# mix_rxd.net
KiCad netlist of a schematic drawn in Altium Designer
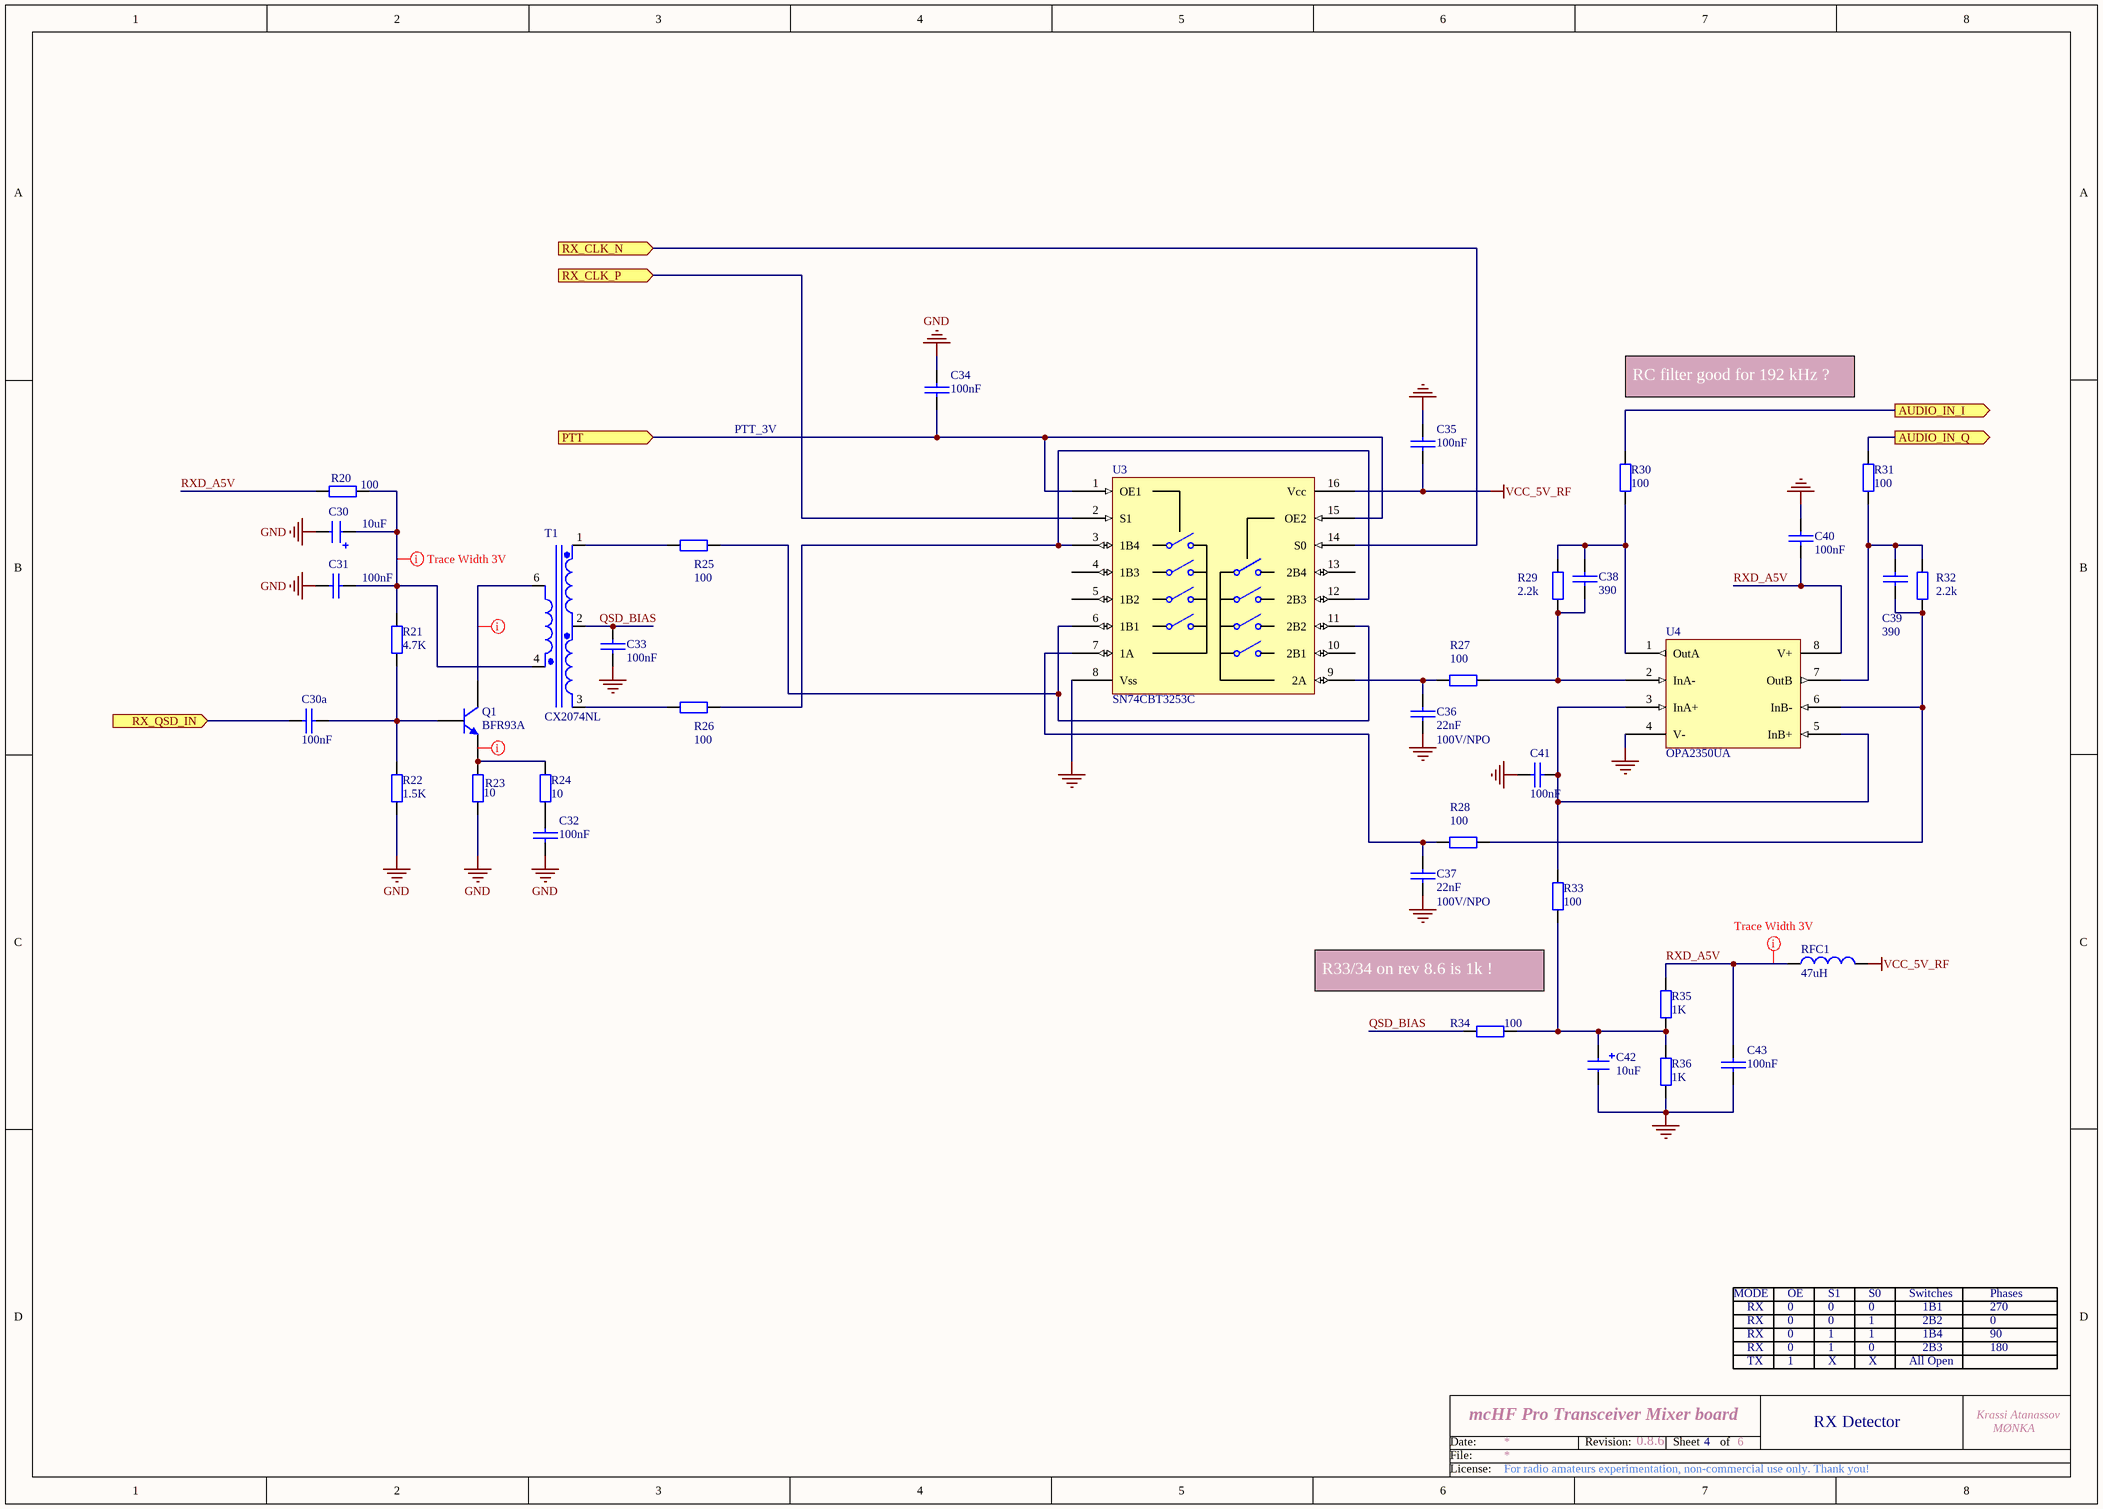
[diagram p0: mix_rxd.SchDoc]

(export (version "E")
  (design (tool "Eeschema 10.0.6"))
  (components
    (comp (ref "C30")
      (value "10uF")
      (footprint "1206_Elec_Cap")
      (description "Electrolitic capacitor")
      (libsource (lib "mcHF_rf") (part "CAP-POL"))
    )
    (comp (ref "C30a")
      (value "100nF")
      (footprint "0805")
      (description "Capacitor")
      (libsource (lib "mcHF_rf") (part "CAP"))
    )
    (comp (ref "C31")
      (value "100nF")
      (footprint "0805")
      (description "Capacitor")
      (libsource (lib "mcHF_rf") (part "CAP"))
    )
    (comp (ref "C32")
      (value "100nF")
      (footprint "0805")
      (description "Capacitor")
      (libsource (lib "mcHF_rf") (part "CAP"))
    )
    (comp (ref "C33")
      (value "100nF")
      (footprint "0805")
      (description "Capacitor")
      (libsource (lib "mcHF_rf") (part "CAP"))
    )
    (comp (ref "C34")
      (value "100nF")
      (footprint "0805")
      (description "Capacitor")
      (libsource (lib "mcHF_rf") (part "CAP"))
    )
    (comp (ref "C35")
      (value "100nF")
      (footprint "0805")
      (description "Capacitor")
      (libsource (lib "mcHF_rf") (part "CAP"))
    )
    (comp (ref "C36")
      (value "22nF")
      (footprint "CAP_B")
      (description "Capacitor")
      (fields (field (name "VOLTAGE") "100V/NPO"))
      (libsource (lib "mcHF_rf") (part "CAP"))
    )
    (comp (ref "C37")
      (value "22nF")
      (footprint "CAP_B")
      (description "Capacitor")
      (fields (field (name "VOLTAGE") "100V/NPO"))
      (libsource (lib "mcHF_rf") (part "CAP"))
    )
    (comp (ref "C38")
      (value "390")
      (footprint "0805")
      (description "Capacitor")
      (libsource (lib "mcHF_rf") (part "CAP"))
    )
    (comp (ref "C39")
      (value "390")
      (footprint "0805")
      (description "Capacitor")
      (libsource (lib "mcHF_rf") (part "CAP"))
    )
    (comp (ref "C40")
      (value "100nF")
      (footprint "0805")
      (description "Capacitor")
      (libsource (lib "mcHF_rf") (part "CAP"))
    )
    (comp (ref "C41")
      (value "100nF")
      (footprint "0805")
      (description "Capacitor")
      (libsource (lib "mcHF_rf") (part "CAP"))
    )
    (comp (ref "C42")
      (value "10uF")
      (footprint "1206_Elec_Cap")
      (description "Electrolitic capacitor")
      (libsource (lib "mcHF_rf") (part "CAP-POL"))
    )
    (comp (ref "C43")
      (value "100nF")
      (footprint "0805")
      (description "Capacitor")
      (libsource (lib "mcHF_rf") (part "CAP"))
    )
    (comp (ref "Q1")
      (value "BFR93A")
      (footprint "SOT-23")
      (description "TRANSISTOR, RF, NPN, 12V, 0.035MA,SOT-23")
      (libsource (lib "mcHF_rf") (part "BFR93A"))
    )
    (comp (ref "R20")
      (value "100")
      (footprint "0805")
      (description "Resistor")
      (libsource (lib "") (part "RES_3"))
    )
    (comp (ref "R21")
      (value "4.7K")
      (footprint "0805")
      (description "Resistor")
      (libsource (lib "") (part "RES_2"))
    )
    (comp (ref "R22")
      (value "1.5K")
      (footprint "0805")
      (description "Resistor")
      (libsource (lib "") (part "RES_2"))
    )
    (comp (ref "R23")
      (value "10")
      (footprint "0805")
      (description "Resistor")
      (libsource (lib "mcHF_rf") (part "RES"))
    )
    (comp (ref "R24")
      (value "10")
      (footprint "0805")
      (description "Resistor")
      (libsource (lib "mcHF_rf") (part "RES"))
    )
    (comp (ref "R25")
      (value "100")
      (footprint "0805")
      (description "Resistor")
      (libsource (lib "") (part "RES_3"))
    )
    (comp (ref "R26")
      (value "100")
      (footprint "0805")
      (description "Resistor")
      (libsource (lib "") (part "RES_3"))
    )
    (comp (ref "R27")
      (value "100")
      (footprint "0805")
      (description "Resistor")
      (libsource (lib "") (part "RES_3"))
    )
    (comp (ref "R28")
      (value "100")
      (footprint "0805")
      (description "Resistor")
      (libsource (lib "") (part "RES_3"))
    )
    (comp (ref "R29")
      (value "2.2k")
      (footprint "0805")
      (description "Resistor")
      (libsource (lib "mcHF_rf") (part "RES"))
    )
    (comp (ref "R30")
      (value "100")
      (footprint "0805")
      (description "Resistor")
      (libsource (lib "mcHF_rf") (part "RES"))
    )
    (comp (ref "R31")
      (value "100")
      (footprint "0805")
      (description "Resistor")
      (libsource (lib "mcHF_rf") (part "RES"))
    )
    (comp (ref "R32")
      (value "2.2k")
      (footprint "0805")
      (description "Resistor")
      (libsource (lib "mcHF_rf") (part "RES"))
    )
    (comp (ref "R33")
      (value "100")
      (footprint "0805")
      (description "Resistor")
      (libsource (lib "mcHF_rf") (part "RES"))
    )
    (comp (ref "R34")
      (value "100")
      (footprint "0805")
      (description "Resistor")
      (libsource (lib "") (part "RES_1"))
    )
    (comp (ref "R35")
      (value "1K")
      (footprint "0805")
      (description "Resistor")
      (libsource (lib "mcHF_rf") (part "RES"))
    )
    (comp (ref "R36")
      (value "1K")
      (footprint "0805")
      (description "Resistor")
      (libsource (lib "mcHF_rf") (part "RES"))
    )
    (comp (ref "RFC1")
      (value "47uH")
      (footprint "0805")
      (description "INDUCTOR, SIGNAL LINE, 4.7UH, 1005")
      (libsource (lib "mcHF_rf") (part "TDK-NLV25T"))
    )
    (comp (ref "T1")
      (value "CX2074NL")
      (footprint "SOP5_NEW1")
      (description "Wideband RF Transformer 1:4")
      (libsource (lib "mcHF_rf") (part "CX2074NL"))
    )
    (comp (ref "U3")
      (value "SN74CBT3253C")
      (footprint "SO-16-Pro")
      (description "Dual 4:1 Demux/Analog Switch")
      (libsource (lib "mcHF_rf") (part "SN74CBT3253C"))
    )
    (comp (ref "U4")
      (value "OPA2350UA")
      (footprint "SO-8")
      (description "High Speed, Single Supply OpAmp")
      (libsource (lib "mcHF_rf") (part "OPA2350UA"))
    )
  )
  (nets
    (net (code "1") (name "/AUDIO_IN_I") (class "Default")
      (node (ref "R30") (pin "2") (pinfunction "2_2") (pintype "passive"))
    )
    (net (code "2") (name "/AUDIO_IN_Q") (class "Default")
      (node (ref "R31") (pin "2") (pinfunction "2_2") (pintype "passive"))
    )
    (net (code "3") (name "/PTT") (class "Default")
      (node (ref "C34") (pin "1") (pinfunction "1_1") (pintype "passive"))
      (node (ref "U3") (pin "1") (pinfunction "OE1_1") (pintype "input"))
      (node (ref "U3") (pin "15") (pinfunction "OE2_15") (pintype "input"))
    )
    (net (code "4") (name "/QSD_BIAS") (class "Default")
      (node (ref "C33") (pin "1") (pinfunction "1_1") (pintype "passive"))
      (node (ref "R34") (pin "2") (pinfunction "2_2") (pintype "passive"))
      (node (ref "T1") (pin "2") (pinfunction "SecCmn_2") (pintype "passive"))
    )
    (net (code "5") (name "/RXD_A5V") (class "Default")
      (node (ref "C40") (pin "2") (pinfunction "2_2") (pintype "passive"))
      (node (ref "C43") (pin "2") (pinfunction "2_2") (pintype "passive"))
      (node (ref "R20") (pin "1") (pinfunction "1_1") (pintype "passive"))
      (node (ref "R35") (pin "2") (pinfunction "2_2") (pintype "passive"))
      (node (ref "RFC1") (pin "1") (pinfunction "1_1") (pintype "passive"))
      (node (ref "U4") (pin "8") (pinfunction "V+_8") (pintype "power_in"))
    )
    (net (code "6") (name "/RX_CLK_N") (class "Default")
      (node (ref "U3") (pin "14") (pinfunction "S0_14") (pintype "input"))
    )
    (net (code "7") (name "/RX_CLK_P") (class "Default")
      (node (ref "U3") (pin "2") (pinfunction "S1_2") (pintype "input"))
    )
    (net (code "8") (name "/RX_QSD_IN") (class "Default")
      (node (ref "C30a") (pin "1") (pinfunction "1_1") (pintype "passive"))
    )
    (net (code "9") (name "GND") (class "Default")
      (node (ref "C30") (pin "2") (pinfunction "2_2") (pintype "passive"))
      (node (ref "C31") (pin "2") (pinfunction "2_2") (pintype "passive"))
      (node (ref "C32") (pin "1") (pinfunction "1_1") (pintype "passive"))
      (node (ref "C33") (pin "2") (pinfunction "2_2") (pintype "passive"))
      (node (ref "C34") (pin "2") (pinfunction "2_2") (pintype "passive"))
      (node (ref "C35") (pin "2") (pinfunction "2_2") (pintype "passive"))
      (node (ref "C36") (pin "2") (pinfunction "2_2") (pintype "passive"))
      (node (ref "C37") (pin "2") (pinfunction "2_2") (pintype "passive"))
      (node (ref "C40") (pin "1") (pinfunction "1_1") (pintype "passive"))
      (node (ref "C41") (pin "2") (pinfunction "2_2") (pintype "passive"))
      (node (ref "C42") (pin "2") (pinfunction "2_2") (pintype "passive"))
      (node (ref "C43") (pin "1") (pinfunction "1_1") (pintype "passive"))
      (node (ref "R22") (pin "2") (pinfunction "2_2") (pintype "passive"))
      (node (ref "R23") (pin "1") (pinfunction "1_1") (pintype "passive"))
      (node (ref "R36") (pin "1") (pinfunction "1_1") (pintype "passive"))
      (node (ref "U3") (pin "8") (pinfunction "Vss_8") (pintype "power_in"))
      (node (ref "U4") (pin "4") (pinfunction "V-_4") (pintype "power_in"))
    )
    (net (code "10") (name "Net-(C32-Pad2)") (class "Default")
      (node (ref "C32") (pin "2") (pinfunction "2_2") (pintype "passive"))
      (node (ref "R24") (pin "1") (pinfunction "1_1") (pintype "passive"))
    )
    (net (code "11") (name "Net-(C42-Pad1)") (class "Default")
      (node (ref "C42") (pin "1") (pinfunction "1_1") (pintype "passive"))
      (node (ref "R33") (pin "1") (pinfunction "1_1") (pintype "passive"))
      (node (ref "R34") (pin "1") (pinfunction "1_1") (pintype "passive"))
      (node (ref "R35") (pin "1") (pinfunction "1_1") (pintype "passive"))
      (node (ref "R36") (pin "2") (pinfunction "2_2") (pintype "passive"))
    )
    (net (code "12") (name "Net-(Q1-B)") (class "Default")
      (node (ref "C30a") (pin "2") (pinfunction "2_2") (pintype "passive"))
      (node (ref "Q1") (pin "1") (pinfunction "B_1") (pintype "passive"))
      (node (ref "R21") (pin "2") (pinfunction "2_2") (pintype "passive"))
      (node (ref "R22") (pin "1") (pinfunction "1_1") (pintype "passive"))
    )
    (net (code "13") (name "Net-(Q1-C)") (class "Default")
      (node (ref "Q1") (pin "3") (pinfunction "C_3") (pintype "passive"))
      (node (ref "T1") (pin "6") (pinfunction "Pri+_6") (pintype "passive"))
    )
    (net (code "14") (name "Net-(Q1-E)") (class "Default")
      (node (ref "Q1") (pin "2") (pinfunction "E_2") (pintype "passive"))
      (node (ref "R23") (pin "2") (pinfunction "2_2") (pintype "passive"))
      (node (ref "R24") (pin "2") (pinfunction "2_2") (pintype "passive"))
    )
    (net (code "15") (name "Net-(T1-Pri-)") (class "Default")
      (node (ref "C30") (pin "1") (pinfunction "1_1") (pintype "passive"))
      (node (ref "C31") (pin "1") (pinfunction "1_1") (pintype "passive"))
      (node (ref "R20") (pin "2") (pinfunction "2_2") (pintype "passive"))
      (node (ref "R21") (pin "1") (pinfunction "1_1") (pintype "passive"))
      (node (ref "T1") (pin "4") (pinfunction "Pri-_4") (pintype "passive"))
    )
    (net (code "16") (name "Net-(T1-Sec0)") (class "Default")
      (node (ref "R25") (pin "1") (pinfunction "1_1") (pintype "passive"))
      (node (ref "T1") (pin "1") (pinfunction "Sec0_1") (pintype "passive"))
    )
    (net (code "17") (name "Net-(T1-Sec180)") (class "Default")
      (node (ref "R26") (pin "1") (pinfunction "1_1") (pintype "passive"))
      (node (ref "T1") (pin "3") (pinfunction "Sec180_3") (pintype "passive"))
    )
    (net (code "18") (name "Net-(U3-1A)") (class "Default")
      (node (ref "C37") (pin "1") (pinfunction "1_1") (pintype "passive"))
      (node (ref "R28") (pin "1") (pinfunction "1_1") (pintype "passive"))
      (node (ref "U3") (pin "7") (pinfunction "1A_7") (pintype "bidirectional"))
    )
    (net (code "19") (name "Net-(U3-1B1)") (class "Default")
      (node (ref "R25") (pin "2") (pinfunction "2_2") (pintype "passive"))
      (node (ref "U3") (pin "11") (pinfunction "2B2_11") (pintype "bidirectional"))
      (node (ref "U3") (pin "6") (pinfunction "1B1_6") (pintype "bidirectional"))
    )
    (net (code "20") (name "Net-(U3-1B4)") (class "Default")
      (node (ref "R26") (pin "2") (pinfunction "2_2") (pintype "passive"))
      (node (ref "U3") (pin "12") (pinfunction "2B3_12") (pintype "bidirectional"))
      (node (ref "U3") (pin "3") (pinfunction "1B4_3") (pintype "bidirectional"))
    )
    (net (code "21") (name "Net-(U3-2A)") (class "Default")
      (node (ref "C36") (pin "1") (pinfunction "1_1") (pintype "passive"))
      (node (ref "R27") (pin "1") (pinfunction "1_1") (pintype "passive"))
      (node (ref "U3") (pin "9") (pinfunction "2A_9") (pintype "bidirectional"))
    )
    (net (code "22") (name "Net-(U4-InA+)") (class "Default")
      (node (ref "C41") (pin "1") (pinfunction "1_1") (pintype "passive"))
      (node (ref "R33") (pin "2") (pinfunction "2_2") (pintype "passive"))
      (node (ref "U4") (pin "3") (pinfunction "InA+_3") (pintype "input"))
      (node (ref "U4") (pin "5") (pinfunction "InB+_5") (pintype "input"))
    )
    (net (code "23") (name "Net-(U4-InA-)") (class "Default")
      (node (ref "C38") (pin "1") (pinfunction "1_1") (pintype "passive"))
      (node (ref "R27") (pin "2") (pinfunction "2_2") (pintype "passive"))
      (node (ref "R29") (pin "1") (pinfunction "1_1") (pintype "passive"))
      (node (ref "U4") (pin "2") (pinfunction "InA-_2") (pintype "input"))
    )
    (net (code "24") (name "Net-(U4-InB-)") (class "Default")
      (node (ref "C39") (pin "1") (pinfunction "1_1") (pintype "passive"))
      (node (ref "R28") (pin "2") (pinfunction "2_2") (pintype "passive"))
      (node (ref "R32") (pin "1") (pinfunction "1_1") (pintype "passive"))
      (node (ref "U4") (pin "6") (pinfunction "InB-_6") (pintype "input"))
    )
    (net (code "25") (name "Net-(U4-OutA)") (class "Default")
      (node (ref "C38") (pin "2") (pinfunction "2_2") (pintype "passive"))
      (node (ref "R29") (pin "2") (pinfunction "2_2") (pintype "passive"))
      (node (ref "R30") (pin "1") (pinfunction "1_1") (pintype "passive"))
      (node (ref "U4") (pin "1") (pinfunction "OutA_1") (pintype "output"))
    )
    (net (code "26") (name "Net-(U4-OutB)") (class "Default")
      (node (ref "C39") (pin "2") (pinfunction "2_2") (pintype "passive"))
      (node (ref "R31") (pin "1") (pinfunction "1_1") (pintype "passive"))
      (node (ref "R32") (pin "2") (pinfunction "2_2") (pintype "passive"))
      (node (ref "U4") (pin "7") (pinfunction "OutB_7") (pintype "output"))
    )
    (net (code "27") (name "VCC_5V_RF") (class "Default")
      (node (ref "C35") (pin "1") (pinfunction "1_1") (pintype "passive"))
      (node (ref "RFC1") (pin "2") (pinfunction "2_2") (pintype "passive"))
      (node (ref "U3") (pin "16") (pinfunction "Vcc_16") (pintype "power_in"))
    )
    (net (code "28") (name "unconnected-(U3-1B2-Pad5)") (class "Default")
      (node (ref "U3") (pin "5") (pinfunction "1B2_5") (pintype "bidirectional"))
    )
    (net (code "29") (name "unconnected-(U3-1B3-Pad4)") (class "Default")
      (node (ref "U3") (pin "4") (pinfunction "1B3_4") (pintype "bidirectional"))
    )
    (net (code "30") (name "unconnected-(U3-2B1-Pad10)") (class "Default")
      (node (ref "U3") (pin "10") (pinfunction "2B1_10") (pintype "bidirectional"))
    )
    (net (code "31") (name "unconnected-(U3-2B4-Pad13)") (class "Default")
      (node (ref "U3") (pin "13") (pinfunction "2B4_13") (pintype "bidirectional"))
    )
  )
)
